# AFE_Only.net
KiCad netlist of a schematic drawn in EAGLE
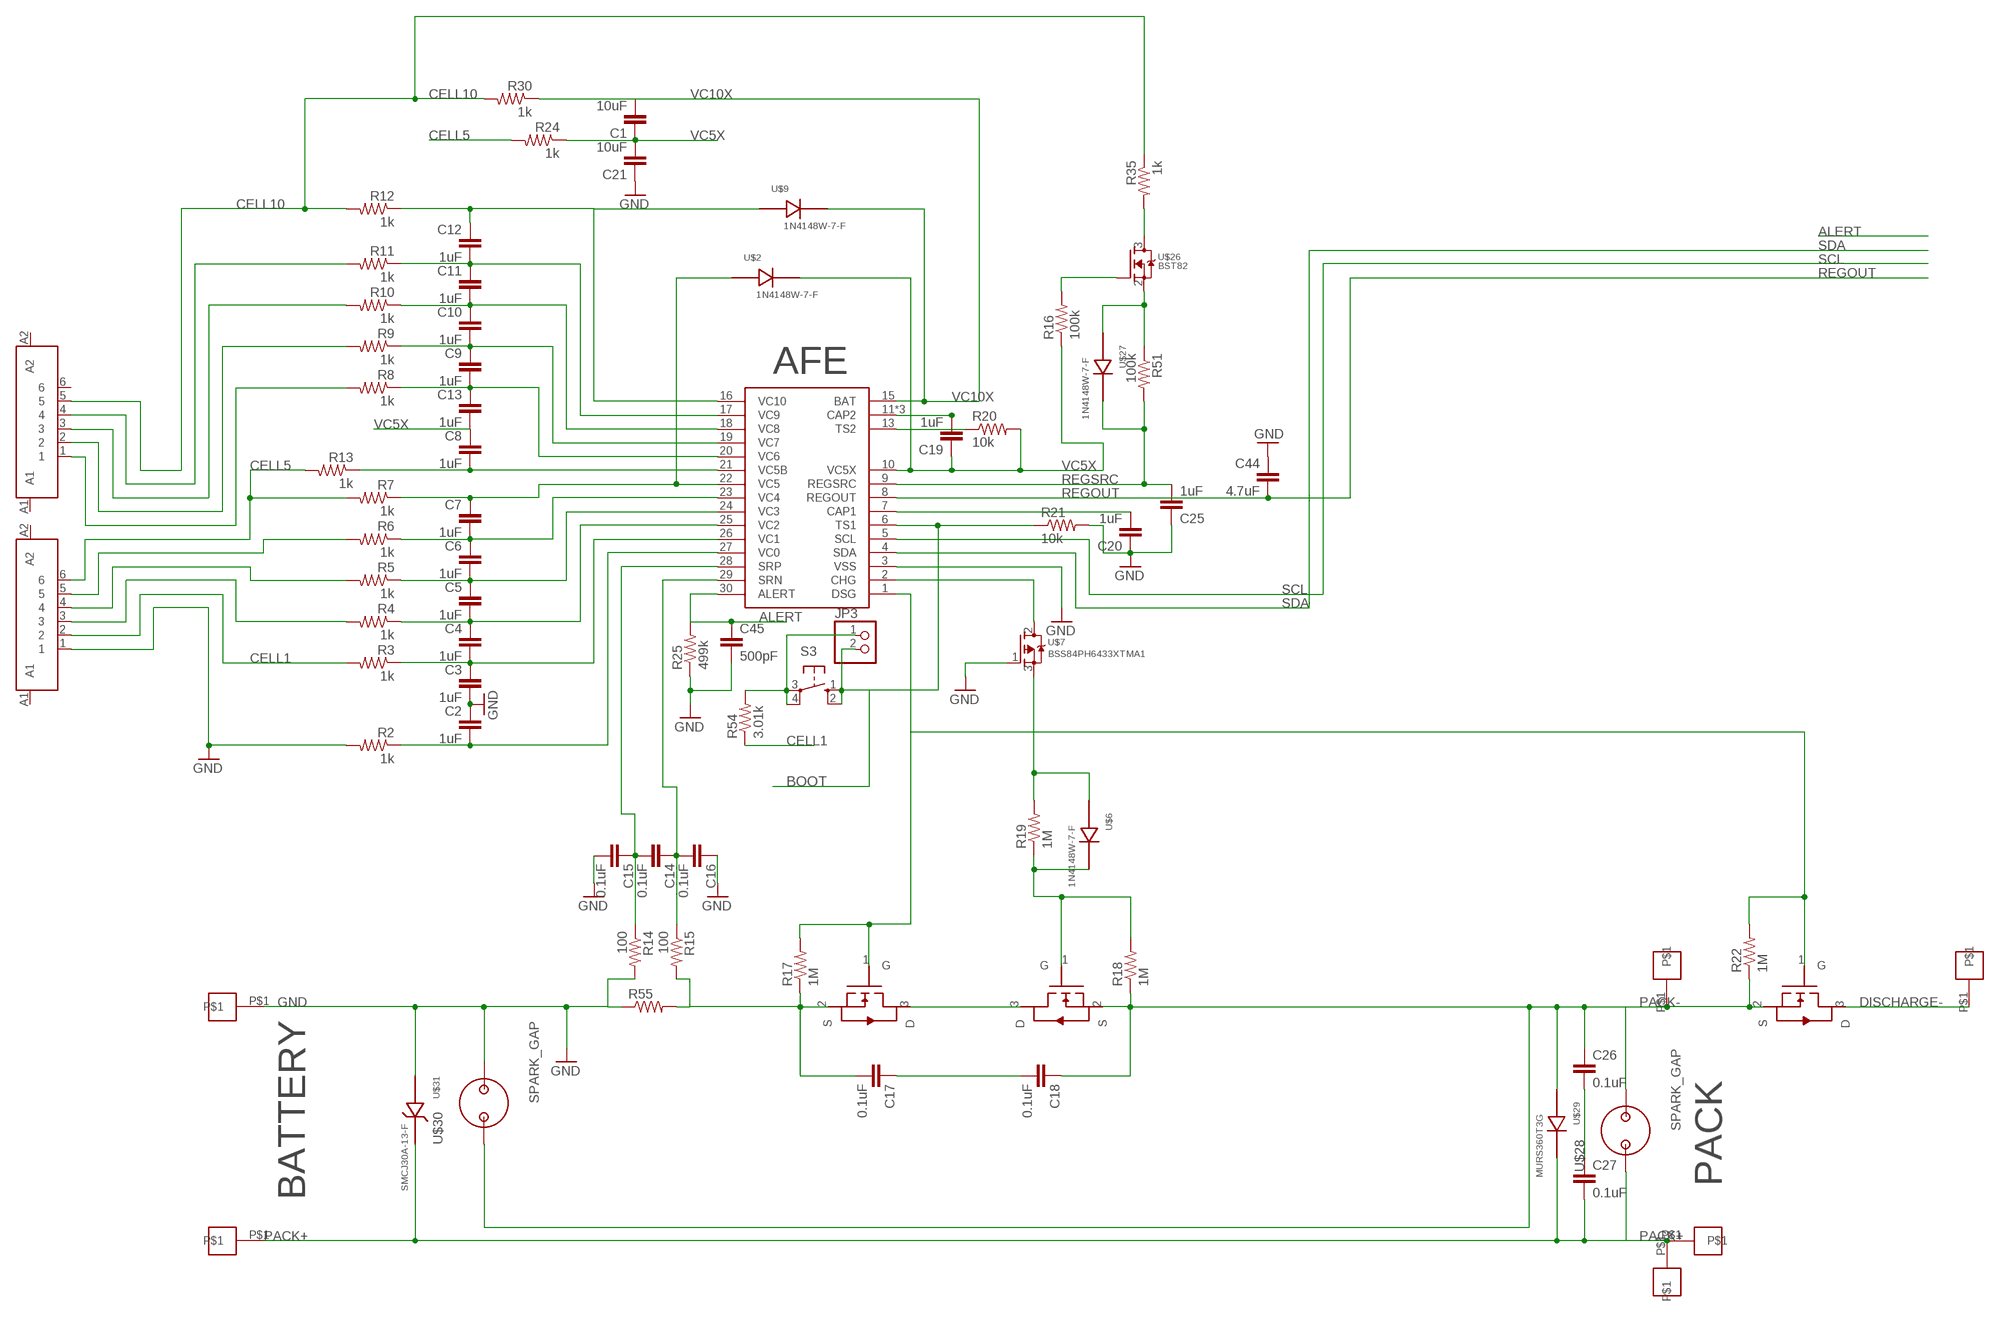
[diagram p0: schematic, sheet 1]
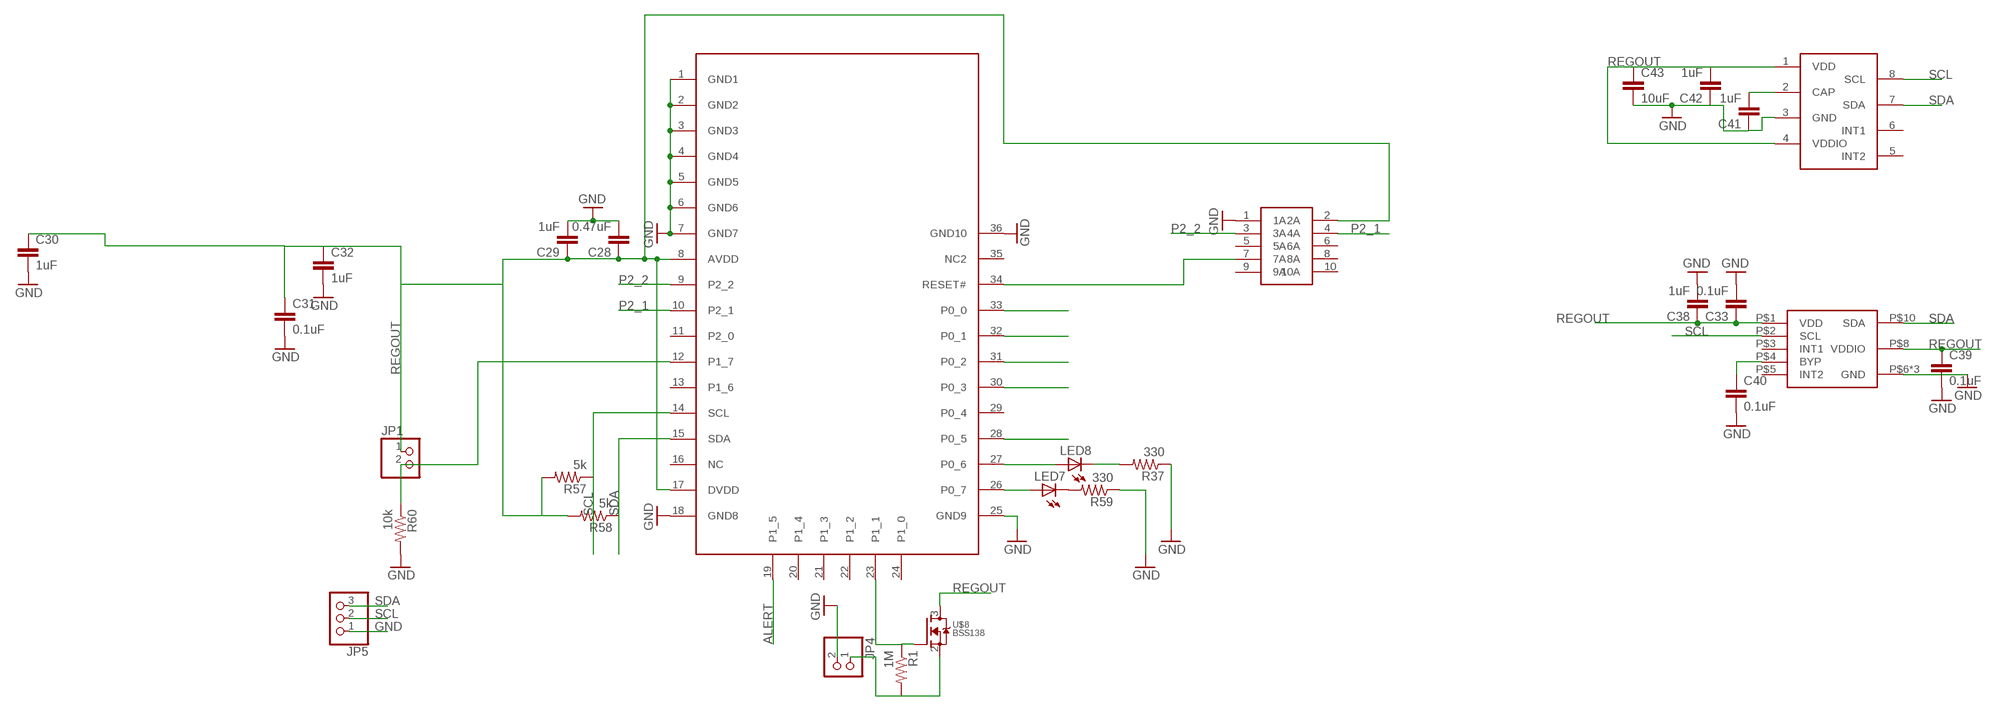
[diagram p1: schematic, sheet 2]

(export (version "E")
  (design (tool "Eeschema 10.0.6"))
  (components
    (comp (ref "C28")
      (value "0.47uF")
      (footprint "eagle-import:C0402")
      (libsource (lib "eagle-import") (part "C-EUC0402"))
    )
    (comp (ref "C29")
      (value "1uF")
      (footprint "eagle-import:C0402")
      (libsource (lib "eagle-import") (part "C-EUC0402"))
    )
    (comp (ref "C30")
      (value "1uF")
      (footprint "eagle-import:C0402")
      (libsource (lib "eagle-import") (part "C-EUC0402"))
    )
    (comp (ref "C31")
      (value "0.1uF")
      (footprint "eagle-import:C0402")
      (libsource (lib "eagle-import") (part "C-EUC0402"))
    )
    (comp (ref "C32")
      (value "1uF")
      (footprint "eagle-import:C0402")
      (libsource (lib "eagle-import") (part "C-EUC0402"))
    )
    (comp (ref "C33")
      (value "0.1uF")
      (footprint "eagle-import:C0402")
      (libsource (lib "eagle-import") (part "C-EUC0402"))
    )
    (comp (ref "C38")
      (value "1uF")
      (footprint "eagle-import:C0402")
      (libsource (lib "eagle-import") (part "C-EUC0402"))
    )
    (comp (ref "C39")
      (value "0.1uF")
      (footprint "eagle-import:C0402")
      (libsource (lib "eagle-import") (part "C-EUC0402"))
    )
    (comp (ref "C40")
      (value "0.1uF")
      (footprint "eagle-import:C0402")
      (libsource (lib "eagle-import") (part "C-EUC0402"))
    )
    (comp (ref "C41")
      (value "1uF")
      (footprint "eagle-import:C0402")
      (libsource (lib "eagle-import") (part "C-EUC0402"))
    )
    (comp (ref "C42")
      (value "1uF")
      (footprint "eagle-import:C0402")
      (libsource (lib "eagle-import") (part "C-EUC0402"))
    )
    (comp (ref "C43")
      (value "10uF")
      (footprint "eagle-import:C0603")
      (libsource (lib "eagle-import") (part "C-EUC0603"))
    )
    (comp (ref "JP1")
      (value "PINHD-1X2")
      (footprint "eagle-import:1X02")
      (libsource (lib "eagle-import") (part "PINHD-1X2"))
    )
    (comp (ref "JP4")
      (value "PINHD-1X2")
      (footprint "eagle-import:1X02")
      (libsource (lib "eagle-import") (part "PINHD-1X2"))
    )
    (comp (ref "JP5")
      (value "PINHD-1X3")
      (footprint "eagle-import:1X03")
      (libsource (lib "eagle-import") (part "PINHD-1X3"))
    )
    (comp (ref "LED7")
      (value "LEDCHIP-LED0603")
      (footprint "eagle-import:CHIP-LED0603")
      (libsource (lib "eagle-import") (part "LEDCHIP-LED0603"))
    )
    (comp (ref "LED8")
      (value "LEDCHIP-LED0603")
      (footprint "eagle-import:CHIP-LED0603")
      (libsource (lib "eagle-import") (part "LEDCHIP-LED0603"))
    )
    (comp (ref "R1")
      (value "1M")
      (footprint "eagle-import:R0402")
      (libsource (lib "eagle-import") (part "R-US_R0402"))
    )
    (comp (ref "R37")
      (value "330")
      (footprint "eagle-import:R0402")
      (libsource (lib "eagle-import") (part "R-US_R0402"))
    )
    (comp (ref "R57")
      (value "5k")
      (footprint "eagle-import:R0402")
      (libsource (lib "eagle-import") (part "R-US_R0402"))
    )
    (comp (ref "R58")
      (value "5k")
      (footprint "eagle-import:R0402")
      (libsource (lib "eagle-import") (part "R-US_R0402"))
    )
    (comp (ref "R59")
      (value "330")
      (footprint "eagle-import:R0402")
      (libsource (lib "eagle-import") (part "R-US_R0402"))
    )
    (comp (ref "R60")
      (value "10k")
      (footprint "eagle-import:R0402")
      (libsource (lib "eagle-import") (part "R-US_R0402"))
    )
    (comp (ref "U$8")
      (value "BSS138")
      (footprint "eagle-import:SOT23-3")
      (libsource (lib "eagle-import") (part "BSS138"))
    )
    (comp (ref "U$20")
      (value "BLE113")
      (footprint "eagle-import:BLUEGIGA")
      (libsource (lib "eagle-import") (part "BLE113"))
    )
    (comp (ref "U$22")
      (value "RIBBON_10POS_MALE")
      (footprint "eagle-import:RIBBON_10POS_MALE")
      (libsource (lib "eagle-import") (part "RIBBON_10POS_MALE"))
    )
    (comp (ref "U$25")
      (value "MLP3115A2")
      (footprint "eagle-import:MLP3115A2")
      (libsource (lib "eagle-import") (part "MLP3115A2"))
    )
    (comp (ref "U$32")
      (value "MMA8653FC")
      (footprint "eagle-import:10-DFN2X2")
      (libsource (lib "eagle-import") (part "MMA8653FC"))
    )
    (comp (ref "C1")
      (value "10uF")
      (footprint "eagle-import:C1210")
      (libsource (lib "eagle-import") (part "C-EUC1210"))
    )
    (comp (ref "C2")
      (value "1uF")
      (footprint "eagle-import:C0805")
      (libsource (lib "eagle-import") (part "C-EUC0805"))
    )
    (comp (ref "C3")
      (value "1uF")
      (footprint "eagle-import:C0805")
      (libsource (lib "eagle-import") (part "C-EUC0805"))
    )
    (comp (ref "C4")
      (value "1uF")
      (footprint "eagle-import:C0805")
      (libsource (lib "eagle-import") (part "C-EUC0805"))
    )
    (comp (ref "C5")
      (value "1uF")
      (footprint "eagle-import:C0805")
      (libsource (lib "eagle-import") (part "C-EUC0805"))
    )
    (comp (ref "C6")
      (value "1uF")
      (footprint "eagle-import:C0805")
      (libsource (lib "eagle-import") (part "C-EUC0805"))
    )
    (comp (ref "C7")
      (value "1uF")
      (footprint "eagle-import:C0805")
      (libsource (lib "eagle-import") (part "C-EUC0805"))
    )
    (comp (ref "C8")
      (value "1uF")
      (footprint "eagle-import:C0805")
      (libsource (lib "eagle-import") (part "C-EUC0805"))
    )
    (comp (ref "C9")
      (value "1uF")
      (footprint "eagle-import:C0805")
      (libsource (lib "eagle-import") (part "C-EUC0805"))
    )
    (comp (ref "C10")
      (value "1uF")
      (footprint "eagle-import:C0805")
      (libsource (lib "eagle-import") (part "C-EUC0805"))
    )
    (comp (ref "C11")
      (value "1uF")
      (footprint "eagle-import:C0805")
      (libsource (lib "eagle-import") (part "C-EUC0805"))
    )
    (comp (ref "C12")
      (value "1uF")
      (footprint "eagle-import:C0805")
      (libsource (lib "eagle-import") (part "C-EUC0805"))
    )
    (comp (ref "C13")
      (value "1uF")
      (footprint "eagle-import:C0805")
      (libsource (lib "eagle-import") (part "C-EUC0805"))
    )
    (comp (ref "C14")
      (value "0.1uF")
      (footprint "eagle-import:C0805")
      (libsource (lib "eagle-import") (part "C-EUC0805"))
    )
    (comp (ref "C15")
      (value "0.1uF")
      (footprint "eagle-import:C0805")
      (libsource (lib "eagle-import") (part "C-EUC0805"))
    )
    (comp (ref "C16")
      (value "0.1uF")
      (footprint "eagle-import:C0805")
      (libsource (lib "eagle-import") (part "C-EUC0805"))
    )
    (comp (ref "C17")
      (value "0.1uF")
      (footprint "eagle-import:C0805")
      (libsource (lib "eagle-import") (part "C-EUC0805"))
    )
    (comp (ref "C18")
      (value "0.1uF")
      (footprint "eagle-import:C0805")
      (libsource (lib "eagle-import") (part "C-EUC0805"))
    )
    (comp (ref "C19")
      (value "1uF")
      (footprint "eagle-import:C0805")
      (libsource (lib "eagle-import") (part "C-EUC0805"))
    )
    (comp (ref "C20")
      (value "1uF")
      (footprint "eagle-import:C0805")
      (libsource (lib "eagle-import") (part "C-EUC0805"))
    )
    (comp (ref "C21")
      (value "10uF")
      (footprint "eagle-import:C1210")
      (libsource (lib "eagle-import") (part "C-EUC1210"))
    )
    (comp (ref "C25")
      (value "1uF")
      (footprint "eagle-import:C0805")
      (libsource (lib "eagle-import") (part "C-EUC0805"))
    )
    (comp (ref "C26")
      (value "0.1uF")
      (footprint "eagle-import:C0805")
      (libsource (lib "eagle-import") (part "C-EUC0805"))
    )
    (comp (ref "C27")
      (value "0.1uF")
      (footprint "eagle-import:C0805")
      (libsource (lib "eagle-import") (part "C-EUC0805"))
    )
    (comp (ref "C44")
      (value "4.7uF")
      (footprint "eagle-import:C0805")
      (libsource (lib "eagle-import") (part "C-EUC0805"))
    )
    (comp (ref "C45")
      (value "500pF")
      (footprint "eagle-import:C0603")
      (libsource (lib "eagle-import") (part "C-EUC0603"))
    )
    (comp (ref "JP3")
      (value "PINHD-1X2")
      (footprint "eagle-import:1X02")
      (libsource (lib "eagle-import") (part "PINHD-1X2"))
    )
    (comp (ref "R2")
      (value "1k")
      (footprint "eagle-import:R1206")
      (libsource (lib "eagle-import") (part "R-US_R1206"))
    )
    (comp (ref "R3")
      (value "1k")
      (footprint "eagle-import:R1206")
      (libsource (lib "eagle-import") (part "R-US_R1206"))
    )
    (comp (ref "R4")
      (value "1k")
      (footprint "eagle-import:R1206")
      (libsource (lib "eagle-import") (part "R-US_R1206"))
    )
    (comp (ref "R5")
      (value "1k")
      (footprint "eagle-import:R1206")
      (libsource (lib "eagle-import") (part "R-US_R1206"))
    )
    (comp (ref "R6")
      (value "1k")
      (footprint "eagle-import:R1206")
      (libsource (lib "eagle-import") (part "R-US_R1206"))
    )
    (comp (ref "R7")
      (value "1k")
      (footprint "eagle-import:R1206")
      (libsource (lib "eagle-import") (part "R-US_R1206"))
    )
    (comp (ref "R8")
      (value "1k")
      (footprint "eagle-import:R1206")
      (libsource (lib "eagle-import") (part "R-US_R1206"))
    )
    (comp (ref "R9")
      (value "1k")
      (footprint "eagle-import:R1206")
      (libsource (lib "eagle-import") (part "R-US_R1206"))
    )
    (comp (ref "R10")
      (value "1k")
      (footprint "eagle-import:R1206")
      (libsource (lib "eagle-import") (part "R-US_R1206"))
    )
    (comp (ref "R11")
      (value "1k")
      (footprint "eagle-import:R1206")
      (libsource (lib "eagle-import") (part "R-US_R1206"))
    )
    (comp (ref "R12")
      (value "1k")
      (footprint "eagle-import:R1206")
      (libsource (lib "eagle-import") (part "R-US_R1206"))
    )
    (comp (ref "R13")
      (value "1k")
      (footprint "eagle-import:R1206")
      (libsource (lib "eagle-import") (part "R-US_R1206"))
    )
    (comp (ref "R14")
      (value "100")
      (footprint "eagle-import:R0805")
      (libsource (lib "eagle-import") (part "R-US_R0805"))
    )
    (comp (ref "R15")
      (value "100")
      (footprint "eagle-import:R0805")
      (libsource (lib "eagle-import") (part "R-US_R0805"))
    )
    (comp (ref "R16")
      (value "100k")
      (footprint "eagle-import:R0805")
      (libsource (lib "eagle-import") (part "R-US_R0805"))
    )
    (comp (ref "R17")
      (value "1M")
      (footprint "eagle-import:R1206")
      (libsource (lib "eagle-import") (part "R-US_R1206"))
    )
    (comp (ref "R18")
      (value "1M")
      (footprint "eagle-import:R1206")
      (libsource (lib "eagle-import") (part "R-US_R1206"))
    )
    (comp (ref "R19")
      (value "1M")
      (footprint "eagle-import:R1206")
      (libsource (lib "eagle-import") (part "R-US_R1206"))
    )
    (comp (ref "R20")
      (value "10k")
      (footprint "eagle-import:R0805")
      (libsource (lib "eagle-import") (part "R-US_R0805"))
    )
    (comp (ref "R21")
      (value "10k")
      (footprint "eagle-import:R0805")
      (libsource (lib "eagle-import") (part "R-US_R0805"))
    )
    (comp (ref "R22")
      (value "1M")
      (footprint "eagle-import:R1206")
      (libsource (lib "eagle-import") (part "R-US_R1206"))
    )
    (comp (ref "R24")
      (value "1k")
      (footprint "eagle-import:R1206")
      (libsource (lib "eagle-import") (part "R-US_R1206"))
    )
    (comp (ref "R25")
      (value "499k")
      (footprint "eagle-import:R0603")
      (libsource (lib "eagle-import") (part "R-US_R0603"))
    )
    (comp (ref "R30")
      (value "1k")
      (footprint "eagle-import:R1206")
      (libsource (lib "eagle-import") (part "R-US_R1206"))
    )
    (comp (ref "R35")
      (value "1k")
      (footprint "eagle-import:R1206")
      (libsource (lib "eagle-import") (part "R-US_R1206"))
    )
    (comp (ref "R51")
      (value "100k")
      (footprint "eagle-import:R0805")
      (libsource (lib "eagle-import") (part "R-US_R0805"))
    )
    (comp (ref "R54")
      (value "3.01k")
      (footprint "eagle-import:R1206")
      (libsource (lib "eagle-import") (part "R-US_R1206"))
    )
    (comp (ref "R55")
      (value "R-US_R2512")
      (footprint "eagle-import:R2512")
      (libsource (lib "eagle-import") (part "R-US_R2512"))
    )
    (comp (ref "S3")
      (value "10-XX")
      (footprint "eagle-import:B3F-10XX")
      (fields (field (name "MPN") "B3F-1000"))
      (libsource (lib "eagle-import") (part "10-XX"))
    )
    (comp (ref "U$1")
      (value "BQ76930")
      (footprint "eagle-import:SOIC-30")
      (libsource (lib "eagle-import") (part "BQ76930"))
    )
    (comp (ref "U$2")
      (value "1N4148W-7-F")
      (footprint "eagle-import:SOD-123")
      (libsource (lib "eagle-import") (part "1N4148W-7-F"))
    )
    (comp (ref "U$3")
      (value "PAD")
      (footprint "eagle-import:PAD")
      (libsource (lib "eagle-import") (part "PAD"))
    )
    (comp (ref "U$4")
      (value "AOB290L")
      (footprint "eagle-import:TO-263")
      (libsource (lib "eagle-import") (part "AOB290L"))
    )
    (comp (ref "U$5")
      (value "AOB290L")
      (footprint "eagle-import:TO-263")
      (libsource (lib "eagle-import") (part "AOB290L"))
    )
    (comp (ref "U$6")
      (value "1N4148W-7-F")
      (footprint "eagle-import:SOD-123")
      (libsource (lib "eagle-import") (part "1N4148W-7-F"))
    )
    (comp (ref "U$7")
      (value "BSS84PH6433XTMA1")
      (footprint "eagle-import:SOT23-3")
      (libsource (lib "eagle-import") (part "BSS84PH6433XTMA1"))
    )
    (comp (ref "U$9")
      (value "1N4148W-7-F")
      (footprint "eagle-import:SOD-123")
      (libsource (lib "eagle-import") (part "1N4148W-7-F"))
    )
    (comp (ref "U$10")
      (value "AOB290L")
      (footprint "eagle-import:TO-263")
      (libsource (lib "eagle-import") (part "AOB290L"))
    )
    (comp (ref "U$24")
      (value "JST_6PIN")
      (footprint "eagle-import:JST_6PIN")
      (libsource (lib "eagle-import") (part "JST_6PIN"))
    )
    (comp (ref "U$26")
      (value "BST82")
      (footprint "eagle-import:SOT23-3")
      (libsource (lib "eagle-import") (part "BST82"))
    )
    (comp (ref "U$27")
      (value "1N4148W-7-F")
      (footprint "eagle-import:SOD-123")
      (libsource (lib "eagle-import") (part "1N4148W-7-F"))
    )
    (comp (ref "U$28")
      (value "SPARK_GAP")
      (footprint "eagle-import:SPARK_GAP")
      (libsource (lib "eagle-import") (part "SPARK_GAP"))
    )
    (comp (ref "U$29")
      (value "MURS360T3G")
      (footprint "eagle-import:SMC(DO-214AB)")
      (libsource (lib "eagle-import") (part "MURS360T3G"))
    )
    (comp (ref "U$30")
      (value "SPARK_GAP")
      (footprint "eagle-import:SPARK_GAP")
      (libsource (lib "eagle-import") (part "SPARK_GAP"))
    )
    (comp (ref "U$31")
      (value "SMCJ30A-13-F")
      (footprint "eagle-import:SMB(DO-214AA)")
      (libsource (lib "eagle-import") (part "SMCJ30A-13-F"))
    )
    (comp (ref "U$33")
      (value "JST_6PIN")
      (footprint "eagle-import:JST_6PIN")
      (libsource (lib "eagle-import") (part "JST_6PIN"))
    )
    (comp (ref "U$35")
      (value "PAD")
      (footprint "eagle-import:PAD")
      (libsource (lib "eagle-import") (part "PAD"))
    )
    (comp (ref "U$36")
      (value "PAD")
      (footprint "eagle-import:PAD")
      (libsource (lib "eagle-import") (part "PAD"))
    )
    (comp (ref "U$37")
      (value "PAD")
      (footprint "eagle-import:PAD")
      (libsource (lib "eagle-import") (part "PAD"))
    )
    (comp (ref "U$38")
      (value "PAD")
      (footprint "eagle-import:PAD")
      (libsource (lib "eagle-import") (part "PAD"))
    )
    (comp (ref "U$39")
      (value "PAD")
      (footprint "eagle-import:PAD")
      (libsource (lib "eagle-import") (part "PAD"))
    )
  )
  (nets
    (net (code "1") (name "ALERT") (class "Default")
      (node (ref "C45") (pin "1") (pinfunction "1_1") (pintype "passive"))
      (node (ref "R25") (pin "2") (pinfunction "2_2") (pintype "passive"))
      (node (ref "U$1") (pin "30") (pinfunction "ALERT_30") (pintype "bidirectional"))
      (node (ref "U$20") (pin "19") (pinfunction "P1_5_19") (pintype "bidirectional"))
    )
    (net (code "2") (name "BOOT") (class "Default")
      (node (ref "JP3") (pin "2") (pinfunction "2_2") (pintype "passive"))
      (node (ref "R21") (pin "1") (pinfunction "1_1") (pintype "passive"))
      (node (ref "S3") (pin "1") (pinfunction "S_1") (pintype "passive"))
      (node (ref "S3") (pin "2") (pinfunction "S1_2") (pintype "passive"))
      (node (ref "U$1") (pin "6") (pinfunction "TS1_6") (pintype "bidirectional"))
    )
    (net (code "3") (name "CELL1") (class "Default")
      (node (ref "R3") (pin "2") (pinfunction "2_2") (pintype "passive"))
      (node (ref "R54") (pin "1") (pinfunction "1_1") (pintype "passive"))
      (node (ref "U$33") (pin "2") (pinfunction "2_2") (pintype "bidirectional"))
    )
    (net (code "4") (name "CELL5") (class "Default")
      (node (ref "R13") (pin "2") (pinfunction "2_2") (pintype "passive"))
      (node (ref "R24") (pin "2") (pinfunction "2_2") (pintype "passive"))
      (node (ref "R7") (pin "2") (pinfunction "2_2") (pintype "passive"))
      (node (ref "U$33") (pin "6") (pinfunction "6_6") (pintype "bidirectional"))
    )
    (net (code "5") (name "CELL10") (class "Default")
      (node (ref "R12") (pin "2") (pinfunction "2_2") (pintype "passive"))
      (node (ref "R30") (pin "2") (pinfunction "2_2") (pintype "passive"))
      (node (ref "R35") (pin "1") (pinfunction "1_1") (pintype "passive"))
      (node (ref "U$24") (pin "5") (pinfunction "5_5") (pintype "bidirectional"))
    )
    (net (code "6") (name "DISCHARGE-") (class "Default")
      (node (ref "U$10") (pin "3") (pinfunction "D_3") (pintype "bidirectional"))
      (node (ref "U$37") (pin "P$1") (pinfunction "P$1_P$1") (pintype "bidirectional"))
    )
    (net (code "7") (name "GND") (class "Default")
      (node (ref "C15") (pin "2") (pinfunction "2_2") (pintype "passive"))
      (node (ref "C16") (pin "1") (pinfunction "1_1") (pintype "passive"))
      (node (ref "C2") (pin "1") (pinfunction "1_1") (pintype "passive"))
      (node (ref "C20") (pin "1") (pinfunction "1_1") (pintype "passive"))
      (node (ref "C21") (pin "1") (pinfunction "1_1") (pintype "passive"))
      (node (ref "C25") (pin "1") (pinfunction "1_1") (pintype "passive"))
      (node (ref "C28") (pin "2") (pinfunction "2_2") (pintype "passive"))
      (node (ref "C29") (pin "2") (pinfunction "2_2") (pintype "passive"))
      (node (ref "C3") (pin "2") (pinfunction "2_2") (pintype "passive"))
      (node (ref "C30") (pin "2") (pinfunction "2_2") (pintype "passive"))
      (node (ref "C31") (pin "2") (pinfunction "2_2") (pintype "passive"))
      (node (ref "C32") (pin "2") (pinfunction "2_2") (pintype "passive"))
      (node (ref "C33") (pin "2") (pinfunction "2_2") (pintype "passive"))
      (node (ref "C38") (pin "2") (pinfunction "2_2") (pintype "passive"))
      (node (ref "C39") (pin "2") (pinfunction "2_2") (pintype "passive"))
      (node (ref "C40") (pin "2") (pinfunction "2_2") (pintype "passive"))
      (node (ref "C41") (pin "1") (pinfunction "1_1") (pintype "passive"))
      (node (ref "C42") (pin "1") (pinfunction "1_1") (pintype "passive"))
      (node (ref "C43") (pin "2") (pinfunction "2_2") (pintype "passive"))
      (node (ref "C44") (pin "1") (pinfunction "1_1") (pintype "passive"))
      (node (ref "C45") (pin "2") (pinfunction "2_2") (pintype "passive"))
      (node (ref "JP4") (pin "2") (pinfunction "2_2") (pintype "passive"))
      (node (ref "JP5") (pin "1") (pinfunction "1_1") (pintype "passive"))
      (node (ref "R14") (pin "2") (pinfunction "2_2") (pintype "passive"))
      (node (ref "R2") (pin "2") (pinfunction "2_2") (pintype "passive"))
      (node (ref "R21") (pin "2") (pinfunction "2_2") (pintype "passive"))
      (node (ref "R25") (pin "1") (pinfunction "1_1") (pintype "passive"))
      (node (ref "R37") (pin "1") (pinfunction "1_1") (pintype "passive"))
      (node (ref "R55") (pin "1") (pinfunction "1_1") (pintype "passive"))
      (node (ref "R59") (pin "1") (pinfunction "1_1") (pintype "passive"))
      (node (ref "R60") (pin "2") (pinfunction "2_2") (pintype "passive"))
      (node (ref "U$1") (pin "3") (pinfunction "VSS_3") (pintype "bidirectional"))
      (node (ref "U$20") (pin "1") (pinfunction "GND1_1") (pintype "bidirectional"))
      (node (ref "U$20") (pin "18") (pinfunction "GND8_18") (pintype "bidirectional"))
      (node (ref "U$20") (pin "2") (pinfunction "GND2_2") (pintype "bidirectional"))
      (node (ref "U$20") (pin "25") (pinfunction "GND9_25") (pintype "bidirectional"))
      (node (ref "U$20") (pin "3") (pinfunction "GND3_3") (pintype "bidirectional"))
      (node (ref "U$20") (pin "36") (pinfunction "GND10_36") (pintype "bidirectional"))
      (node (ref "U$20") (pin "4") (pinfunction "GND4_4") (pintype "bidirectional"))
      (node (ref "U$20") (pin "5") (pinfunction "GND5_5") (pintype "bidirectional"))
      (node (ref "U$20") (pin "6") (pinfunction "GND6_6") (pintype "bidirectional"))
      (node (ref "U$20") (pin "7") (pinfunction "GND7_7") (pintype "bidirectional"))
      (node (ref "U$22") (pin "1") (pinfunction "1A_1") (pintype "bidirectional"))
      (node (ref "U$25") (pin "3") (pinfunction "GND_3") (pintype "bidirectional"))
      (node (ref "U$3") (pin "P$1") (pinfunction "P$1_P$1") (pintype "bidirectional"))
      (node (ref "U$30") (pin "P$2") (pinfunction "P$2_P$2") (pintype "bidirectional"))
      (node (ref "U$31") (pin "P$1") (pinfunction "1_P$1") (pintype "bidirectional"))
      (node (ref "U$32") (pin "P$6") (pinfunction "GND_P$6") (pintype "bidirectional"))
      (node (ref "U$32") (pin "P$7") (pinfunction "GND_P$7") (pintype "bidirectional"))
      (node (ref "U$32") (pin "P$9") (pinfunction "GND_P$9") (pintype "bidirectional"))
      (node (ref "U$33") (pin "1") (pinfunction "1_1") (pintype "bidirectional"))
      (node (ref "U$7") (pin "1") (pinfunction "G_1") (pintype "bidirectional"))
    )
    (net (code "8") (name "Net-(C17-Pad1)") (class "Default")
      (node (ref "C17") (pin "1") (pinfunction "1_1") (pintype "passive"))
      (node (ref "C18") (pin "2") (pinfunction "2_2") (pintype "passive"))
    )
    (net (code "9") (name "Net-(C19-Pad2)") (class "Default")
      (node (ref "C19") (pin "2") (pinfunction "2_2") (pintype "passive"))
      (node (ref "U$1") (pin "11") (pinfunction "CAP2_11") (pintype "bidirectional"))
      (node (ref "U$1") (pin "12") (pinfunction "CAP2_12") (pintype "bidirectional"))
      (node (ref "U$1") (pin "14") (pinfunction "CAP2_14") (pintype "bidirectional"))
    )
    (net (code "10") (name "Net-(C26-Pad2)") (class "Default")
      (node (ref "C26") (pin "2") (pinfunction "2_2") (pintype "passive"))
      (node (ref "C27") (pin "1") (pinfunction "1_1") (pintype "passive"))
    )
    (net (code "11") (name "Net-(LED7-PadC)") (class "Default")
      (node (ref "LED7") (pin "C") (pinfunction "C_C") (pintype "passive"))
      (node (ref "R59") (pin "2") (pinfunction "2_2") (pintype "passive"))
    )
    (net (code "12") (name "Net-(LED8-PadC)") (class "Default")
      (node (ref "LED8") (pin "C") (pinfunction "C_C") (pintype "passive"))
      (node (ref "R37") (pin "2") (pinfunction "2_2") (pintype "passive"))
    )
    (net (code "13") (name "Net-(R4-Pad2)") (class "Default")
      (node (ref "R4") (pin "2") (pinfunction "2_2") (pintype "passive"))
      (node (ref "U$33") (pin "3") (pinfunction "3_3") (pintype "bidirectional"))
    )
    (net (code "14") (name "Net-(R5-Pad2)") (class "Default")
      (node (ref "R5") (pin "2") (pinfunction "2_2") (pintype "passive"))
      (node (ref "U$33") (pin "4") (pinfunction "4_4") (pintype "bidirectional"))
    )
    (net (code "15") (name "Net-(R6-Pad2)") (class "Default")
      (node (ref "R6") (pin "2") (pinfunction "2_2") (pintype "passive"))
      (node (ref "U$33") (pin "5") (pinfunction "5_5") (pintype "bidirectional"))
    )
    (net (code "16") (name "Net-(R8-Pad2)") (class "Default")
      (node (ref "R8") (pin "2") (pinfunction "2_2") (pintype "passive"))
      (node (ref "U$24") (pin "1") (pinfunction "1_1") (pintype "bidirectional"))
    )
    (net (code "17") (name "Net-(R9-Pad2)") (class "Default")
      (node (ref "R9") (pin "2") (pinfunction "2_2") (pintype "passive"))
      (node (ref "U$24") (pin "2") (pinfunction "2_2") (pintype "bidirectional"))
    )
    (net (code "18") (name "Net-(R10-Pad2)") (class "Default")
      (node (ref "R10") (pin "2") (pinfunction "2_2") (pintype "passive"))
      (node (ref "U$24") (pin "3") (pinfunction "3_3") (pintype "bidirectional"))
    )
    (net (code "19") (name "Net-(R11-Pad2)") (class "Default")
      (node (ref "R11") (pin "2") (pinfunction "2_2") (pintype "passive"))
      (node (ref "U$24") (pin "4") (pinfunction "4_4") (pintype "bidirectional"))
    )
    (net (code "20") (name "Net-(S3-P)") (class "Default")
      (node (ref "JP3") (pin "1") (pinfunction "1_1") (pintype "passive"))
      (node (ref "R54") (pin "2") (pinfunction "2_2") (pintype "passive"))
      (node (ref "S3") (pin "3") (pinfunction "P_3") (pintype "passive"))
      (node (ref "S3") (pin "4") (pinfunction "P1_4") (pintype "passive"))
    )
    (net (code "21") (name "Net-(U$1-CAP1)") (class "Default")
      (node (ref "C20") (pin "2") (pinfunction "2_2") (pintype "passive"))
      (node (ref "U$1") (pin "7") (pinfunction "CAP1_7") (pintype "bidirectional"))
    )
    (net (code "22") (name "Net-(U$1-CHG)") (class "Default")
      (node (ref "U$1") (pin "2") (pinfunction "CHG_2") (pintype "bidirectional"))
      (node (ref "U$7") (pin "2") (pinfunction "S_2") (pintype "bidirectional"))
    )
    (net (code "23") (name "Net-(U$1-DSG)") (class "Default")
      (node (ref "R17") (pin "2") (pinfunction "2_2") (pintype "passive"))
      (node (ref "R22") (pin "2") (pinfunction "2_2") (pintype "passive"))
      (node (ref "U$1") (pin "1") (pinfunction "DSG_1") (pintype "bidirectional"))
      (node (ref "U$10") (pin "1") (pinfunction "G_1") (pintype "bidirectional"))
      (node (ref "U$4") (pin "1") (pinfunction "G_1") (pintype "bidirectional"))
    )
    (net (code "24") (name "Net-(U$1-SRN)") (class "Default")
      (node (ref "C14") (pin "1") (pinfunction "1_1") (pintype "passive"))
      (node (ref "C16") (pin "2") (pinfunction "2_2") (pintype "passive"))
      (node (ref "R15") (pin "1") (pinfunction "1_1") (pintype "passive"))
      (node (ref "U$1") (pin "29") (pinfunction "SRN_29") (pintype "bidirectional"))
    )
    (net (code "25") (name "Net-(U$1-SRP)") (class "Default")
      (node (ref "C14") (pin "2") (pinfunction "2_2") (pintype "passive"))
      (node (ref "C15") (pin "1") (pinfunction "1_1") (pintype "passive"))
      (node (ref "R14") (pin "1") (pinfunction "1_1") (pintype "passive"))
      (node (ref "U$1") (pin "28") (pinfunction "SRP_28") (pintype "bidirectional"))
    )
    (net (code "26") (name "Net-(U$1-TS2)") (class "Default")
      (node (ref "R20") (pin "1") (pinfunction "1_1") (pintype "passive"))
      (node (ref "U$1") (pin "13") (pinfunction "TS2_13") (pintype "bidirectional"))
    )
    (net (code "27") (name "Net-(U$1-VC0)") (class "Default")
      (node (ref "C2") (pin "2") (pinfunction "2_2") (pintype "passive"))
      (node (ref "R2") (pin "1") (pinfunction "1_1") (pintype "passive"))
      (node (ref "U$1") (pin "27") (pinfunction "VC0_27") (pintype "bidirectional"))
    )
    (net (code "28") (name "Net-(U$1-VC1)") (class "Default")
      (node (ref "C3") (pin "1") (pinfunction "1_1") (pintype "passive"))
      (node (ref "C4") (pin "2") (pinfunction "2_2") (pintype "passive"))
      (node (ref "R3") (pin "1") (pinfunction "1_1") (pintype "passive"))
      (node (ref "U$1") (pin "26") (pinfunction "VC1_26") (pintype "bidirectional"))
    )
    (net (code "29") (name "Net-(U$1-VC2)") (class "Default")
      (node (ref "C4") (pin "1") (pinfunction "1_1") (pintype "passive"))
      (node (ref "C5") (pin "2") (pinfunction "2_2") (pintype "passive"))
      (node (ref "R4") (pin "1") (pinfunction "1_1") (pintype "passive"))
      (node (ref "U$1") (pin "25") (pinfunction "VC2_25") (pintype "bidirectional"))
    )
    (net (code "30") (name "Net-(U$1-VC3)") (class "Default")
      (node (ref "C5") (pin "1") (pinfunction "1_1") (pintype "passive"))
      (node (ref "C6") (pin "2") (pinfunction "2_2") (pintype "passive"))
      (node (ref "R5") (pin "1") (pinfunction "1_1") (pintype "passive"))
      (node (ref "U$1") (pin "24") (pinfunction "VC3_24") (pintype "bidirectional"))
    )
    (net (code "31") (name "Net-(U$1-VC4)") (class "Default")
      (node (ref "C6") (pin "1") (pinfunction "1_1") (pintype "passive"))
      (node (ref "C7") (pin "2") (pinfunction "2_2") (pintype "passive"))
      (node (ref "R6") (pin "1") (pinfunction "1_1") (pintype "passive"))
      (node (ref "U$1") (pin "23") (pinfunction "VC4_23") (pintype "bidirectional"))
    )
    (net (code "32") (name "Net-(U$1-VC5)") (class "Default")
      (node (ref "C7") (pin "1") (pinfunction "1_1") (pintype "passive"))
      (node (ref "R7") (pin "1") (pinfunction "1_1") (pintype "passive"))
      (node (ref "U$1") (pin "22") (pinfunction "VC5_22") (pintype "bidirectional"))
      (node (ref "U$2") (pin "P$1") (pinfunction "P$1_P$1") (pintype "bidirectional"))
    )
    (net (code "33") (name "Net-(U$1-VC5B)") (class "Default")
      (node (ref "C8") (pin "2") (pinfunction "2_2") (pintype "passive"))
      (node (ref "R13") (pin "1") (pinfunction "1_1") (pintype "passive"))
      (node (ref "U$1") (pin "21") (pinfunction "VC5B_21") (pintype "bidirectional"))
    )
    (net (code "34") (name "Net-(U$1-VC6)") (class "Default")
      (node (ref "C13") (pin "1") (pinfunction "1_1") (pintype "passive"))
      (node (ref "C9") (pin "2") (pinfunction "2_2") (pintype "passive"))
      (node (ref "R8") (pin "1") (pinfunction "1_1") (pintype "passive"))
      (node (ref "U$1") (pin "20") (pinfunction "VC6_20") (pintype "bidirectional"))
    )
    (net (code "35") (name "Net-(U$1-VC7)") (class "Default")
      (node (ref "C10") (pin "2") (pinfunction "2_2") (pintype "passive"))
      (node (ref "C9") (pin "1") (pinfunction "1_1") (pintype "passive"))
      (node (ref "R9") (pin "1") (pinfunction "1_1") (pintype "passive"))
      (node (ref "U$1") (pin "19") (pinfunction "VC7_19") (pintype "bidirectional"))
    )
    (net (code "36") (name "Net-(U$1-VC8)") (class "Default")
      (node (ref "C10") (pin "1") (pinfunction "1_1") (pintype "passive"))
      (node (ref "C11") (pin "2") (pinfunction "2_2") (pintype "passive"))
      (node (ref "R10") (pin "1") (pinfunction "1_1") (pintype "passive"))
      (node (ref "U$1") (pin "18") (pinfunction "VC8_18") (pintype "bidirectional"))
    )
    (net (code "37") (name "Net-(U$1-VC9)") (class "Default")
      (node (ref "C11") (pin "1") (pinfunction "1_1") (pintype "passive"))
      (node (ref "C12") (pin "2") (pinfunction "2_2") (pintype "passive"))
      (node (ref "R11") (pin "1") (pinfunction "1_1") (pintype "passive"))
      (node (ref "U$1") (pin "17") (pinfunction "VC9_17") (pintype "bidirectional"))
    )
    (net (code "38") (name "Net-(U$1-VC10)") (class "Default")
      (node (ref "C12") (pin "1") (pinfunction "1_1") (pintype "passive"))
      (node (ref "R12") (pin "1") (pinfunction "1_1") (pintype "passive"))
      (node (ref "U$1") (pin "16") (pinfunction "VC10_16") (pintype "bidirectional"))
      (node (ref "U$9") (pin "P$1") (pinfunction "P$1_P$1") (pintype "bidirectional"))
    )
    (net (code "39") (name "Net-(U$4-D)") (class "Default")
      (node (ref "U$4") (pin "3") (pinfunction "D_3") (pintype "bidirectional"))
      (node (ref "U$5") (pin "3") (pinfunction "D_3") (pintype "bidirectional"))
    )
    (net (code "40") (name "Net-(U$4-S)") (class "Default")
      (node (ref "C17") (pin "2") (pinfunction "2_2") (pintype "passive"))
      (node (ref "R15") (pin "2") (pinfunction "2_2") (pintype "passive"))
      (node (ref "R17") (pin "1") (pinfunction "1_1") (pintype "passive"))
      (node (ref "R55") (pin "2") (pinfunction "2_2") (pintype "passive"))
      (node (ref "U$4") (pin "2") (pinfunction "S_2") (pintype "bidirectional"))
    )
    (net (code "41") (name "Net-(U$5-G)") (class "Default")
      (node (ref "R18") (pin "2") (pinfunction "2_2") (pintype "passive"))
      (node (ref "R19") (pin "1") (pinfunction "1_1") (pintype "passive"))
      (node (ref "U$5") (pin "1") (pinfunction "G_1") (pintype "bidirectional"))
      (node (ref "U$6") (pin "P$2") (pinfunction "P$2_P$2") (pintype "bidirectional"))
    )
    (net (code "42") (name "Net-(U$7-D)") (class "Default")
      (node (ref "R19") (pin "2") (pinfunction "2_2") (pintype "passive"))
      (node (ref "U$6") (pin "P$1") (pinfunction "P$1_P$1") (pintype "bidirectional"))
      (node (ref "U$7") (pin "3") (pinfunction "D_3") (pintype "bidirectional"))
    )
    (net (code "43") (name "Net-(U$8-S)") (class "Default")
      (node (ref "JP4") (pin "1") (pinfunction "1_1") (pintype "passive"))
      (node (ref "R1") (pin "2") (pinfunction "2_2") (pintype "passive"))
      (node (ref "U$8") (pin "2") (pinfunction "S_2") (pintype "bidirectional"))
    )
    (net (code "44") (name "Net-(U$20-P0_6)") (class "Default")
      (node (ref "LED8") (pin "A") (pinfunction "A_A") (pintype "passive"))
      (node (ref "U$20") (pin "27") (pinfunction "P0_6_27") (pintype "bidirectional"))
    )
    (net (code "45") (name "Net-(U$20-P0_7)") (class "Default")
      (node (ref "LED7") (pin "A") (pinfunction "A_A") (pintype "passive"))
      (node (ref "U$20") (pin "26") (pinfunction "P0_7_26") (pintype "bidirectional"))
    )
    (net (code "46") (name "Net-(U$20-P1_1)") (class "Default")
      (node (ref "R1") (pin "1") (pinfunction "1_1") (pintype "passive"))
      (node (ref "U$20") (pin "23") (pinfunction "P1_1_23") (pintype "bidirectional"))
      (node (ref "U$8") (pin "1") (pinfunction "G_1") (pintype "bidirectional"))
    )
    (net (code "47") (name "Net-(U$20-P1_7)") (class "Default")
      (node (ref "JP1") (pin "2") (pinfunction "2_2") (pintype "passive"))
      (node (ref "R60") (pin "1") (pinfunction "1_1") (pintype "passive"))
      (node (ref "U$20") (pin "12") (pinfunction "P1_7_12") (pintype "bidirectional"))
    )
    (net (code "48") (name "Net-(U$20-RESET#)") (class "Default")
      (node (ref "U$20") (pin "34") (pinfunction "RESET#_34") (pintype "bidirectional"))
      (node (ref "U$22") (pin "7") (pinfunction "7A_7") (pintype "bidirectional"))
    )
    (net (code "49") (name "Net-(U$25-CAP)") (class "Default")
      (node (ref "C41") (pin "2") (pinfunction "2_2") (pintype "passive"))
      (node (ref "U$25") (pin "2") (pinfunction "CAP_2") (pintype "bidirectional"))
    )
    (net (code "50") (name "Net-(U$26-D)") (class "Default")
      (node (ref "R35") (pin "2") (pinfunction "2_2") (pintype "passive"))
      (node (ref "U$26") (pin "3") (pinfunction "D_3") (pintype "bidirectional"))
    )
    (net (code "51") (name "Net-(U$26-G)") (class "Default")
      (node (ref "R16") (pin "2") (pinfunction "2_2") (pintype "passive"))
      (node (ref "U$26") (pin "1") (pinfunction "G_1") (pintype "bidirectional"))
    )
    (net (code "52") (name "Net-(U$26-S)") (class "Default")
      (node (ref "R51") (pin "1") (pinfunction "1_1") (pintype "passive"))
      (node (ref "U$26") (pin "2") (pinfunction "S_2") (pintype "bidirectional"))
      (node (ref "U$27") (pin "P$1") (pinfunction "P$1_P$1") (pintype "bidirectional"))
    )
    (net (code "53") (name "Net-(U$32-BYP)") (class "Default")
      (node (ref "C40") (pin "1") (pinfunction "1_1") (pintype "passive"))
      (node (ref "U$32") (pin "P$4") (pinfunction "BYP_P$4") (pintype "bidirectional"))
    )
    (net (code "54") (name "P2_1") (class "Default")
      (node (ref "U$20") (pin "10") (pinfunction "P2_1_10") (pintype "bidirectional"))
      (node (ref "U$22") (pin "4") (pinfunction "4A_4") (pintype "bidirectional"))
    )
    (net (code "55") (name "P2_2") (class "Default")
      (node (ref "U$20") (pin "9") (pinfunction "P2_2_9") (pintype "bidirectional"))
      (node (ref "U$22") (pin "3") (pinfunction "3A_3") (pintype "bidirectional"))
    )
    (net (code "56") (name "PACK+") (class "Default")
      (node (ref "C27") (pin "2") (pinfunction "2_2") (pintype "passive"))
      (node (ref "U$28") (pin "P$1") (pinfunction "P$1_P$1") (pintype "bidirectional"))
      (node (ref "U$29") (pin "2") (pinfunction "P$2_2") (pintype "bidirectional"))
      (node (ref "U$31") (pin "P$2") (pinfunction "2_P$2") (pintype "bidirectional"))
      (node (ref "U$35") (pin "P$1") (pinfunction "P$1_P$1") (pintype "bidirectional"))
      (node (ref "U$36") (pin "P$1") (pinfunction "P$1_P$1") (pintype "bidirectional"))
      (node (ref "U$39") (pin "P$1") (pinfunction "P$1_P$1") (pintype "bidirectional"))
    )
    (net (code "57") (name "PACK-") (class "Default")
      (node (ref "C18") (pin "1") (pinfunction "1_1") (pintype "passive"))
      (node (ref "C26") (pin "1") (pinfunction "1_1") (pintype "passive"))
      (node (ref "R18") (pin "1") (pinfunction "1_1") (pintype "passive"))
      (node (ref "R22") (pin "1") (pinfunction "1_1") (pintype "passive"))
      (node (ref "U$10") (pin "2") (pinfunction "S_2") (pintype "bidirectional"))
      (node (ref "U$28") (pin "P$2") (pinfunction "P$2_P$2") (pintype "bidirectional"))
      (node (ref "U$29") (pin "1") (pinfunction "P$1_1") (pintype "bidirectional"))
      (node (ref "U$30") (pin "P$1") (pinfunction "P$1_P$1") (pintype "bidirectional"))
      (node (ref "U$38") (pin "P$1") (pinfunction "P$1_P$1") (pintype "bidirectional"))
      (node (ref "U$5") (pin "2") (pinfunction "S_2") (pintype "bidirectional"))
    )
    (net (code "58") (name "REGOUT") (class "Default")
      (node (ref "C28") (pin "1") (pinfunction "1_1") (pintype "passive"))
      (node (ref "C29") (pin "1") (pinfunction "1_1") (pintype "passive"))
      (node (ref "C30") (pin "1") (pinfunction "1_1") (pintype "passive"))
      (node (ref "C31") (pin "1") (pinfunction "1_1") (pintype "passive"))
      (node (ref "C32") (pin "1") (pinfunction "1_1") (pintype "passive"))
      (node (ref "C33") (pin "1") (pinfunction "1_1") (pintype "passive"))
      (node (ref "C38") (pin "1") (pinfunction "1_1") (pintype "passive"))
      (node (ref "C39") (pin "1") (pinfunction "1_1") (pintype "passive"))
      (node (ref "C42") (pin "2") (pinfunction "2_2") (pintype "passive"))
      (node (ref "C43") (pin "1") (pinfunction "1_1") (pintype "passive"))
      (node (ref "C44") (pin "2") (pinfunction "2_2") (pintype "passive"))
      (node (ref "JP1") (pin "1") (pinfunction "1_1") (pintype "passive"))
      (node (ref "R57") (pin "2") (pinfunction "2_2") (pintype "passive"))
      (node (ref "R58") (pin "2") (pinfunction "2_2") (pintype "passive"))
      (node (ref "U$1") (pin "8") (pinfunction "REGOUT_8") (pintype "bidirectional"))
      (node (ref "U$20") (pin "17") (pinfunction "DVDD_17") (pintype "bidirectional"))
      (node (ref "U$20") (pin "8") (pinfunction "AVDD_8") (pintype "bidirectional"))
      (node (ref "U$22") (pin "2") (pinfunction "2A_2") (pintype "bidirectional"))
      (node (ref "U$25") (pin "1") (pinfunction "VDD_1") (pintype "bidirectional"))
      (node (ref "U$25") (pin "4") (pinfunction "VDDIO_4") (pintype "bidirectional"))
      (node (ref "U$32") (pin "P$1") (pinfunction "VDD_P$1") (pintype "bidirectional"))
      (node (ref "U$32") (pin "P$8") (pinfunction "VDDIO_P$8") (pintype "bidirectional"))
      (node (ref "U$8") (pin "3") (pinfunction "D_3") (pintype "bidirectional"))
    )
    (net (code "59") (name "REGSRC") (class "Default")
      (node (ref "C25") (pin "2") (pinfunction "2_2") (pintype "passive"))
      (node (ref "R51") (pin "2") (pinfunction "2_2") (pintype "passive"))
      (node (ref "U$1") (pin "9") (pinfunction "REGSRC_9") (pintype "bidirectional"))
      (node (ref "U$27") (pin "P$2") (pinfunction "P$2_P$2") (pintype "bidirectional"))
    )
    (net (code "60") (name "SCL") (class "Default")
      (node (ref "JP5") (pin "2") (pinfunction "2_2") (pintype "passive"))
      (node (ref "R57") (pin "1") (pinfunction "1_1") (pintype "passive"))
      (node (ref "U$1") (pin "5") (pinfunction "SCL_5") (pintype "bidirectional"))
      (node (ref "U$20") (pin "14") (pinfunction "SCL_14") (pintype "bidirectional"))
      (node (ref "U$25") (pin "8") (pinfunction "SCL_8") (pintype "bidirectional"))
      (node (ref "U$32") (pin "P$2") (pinfunction "SCL_P$2") (pintype "bidirectional"))
    )
    (net (code "61") (name "SDA") (class "Default")
      (node (ref "JP5") (pin "3") (pinfunction "3_3") (pintype "passive"))
      (node (ref "R58") (pin "1") (pinfunction "1_1") (pintype "passive"))
      (node (ref "U$1") (pin "4") (pinfunction "SDA_4") (pintype "bidirectional"))
      (node (ref "U$20") (pin "15") (pinfunction "SDA_15") (pintype "bidirectional"))
      (node (ref "U$25") (pin "7") (pinfunction "SDA_7") (pintype "bidirectional"))
      (node (ref "U$32") (pin "P$10") (pinfunction "SDA_P$10") (pintype "bidirectional"))
    )
    (net (code "62") (name "VC5X") (class "Default")
      (node (ref "C1") (pin "1") (pinfunction "1_1") (pintype "passive"))
      (node (ref "C13") (pin "2") (pinfunction "2_2") (pintype "passive"))
      (node (ref "C19") (pin "1") (pinfunction "1_1") (pintype "passive"))
      (node (ref "C21") (pin "2") (pinfunction "2_2") (pintype "passive"))
      (node (ref "C8") (pin "1") (pinfunction "1_1") (pintype "passive"))
      (node (ref "R16") (pin "1") (pinfunction "1_1") (pintype "passive"))
      (node (ref "R20") (pin "2") (pinfunction "2_2") (pintype "passive"))
      (node (ref "R24") (pin "1") (pinfunction "1_1") (pintype "passive"))
      (node (ref "U$1") (pin "10") (pinfunction "VC5X_10") (pintype "bidirectional"))
      (node (ref "U$2") (pin "P$2") (pinfunction "P$2_P$2") (pintype "bidirectional"))
    )
    (net (code "63") (name "VC10X") (class "Default")
      (node (ref "C1") (pin "2") (pinfunction "2_2") (pintype "passive"))
      (node (ref "R30") (pin "1") (pinfunction "1_1") (pintype "passive"))
      (node (ref "U$1") (pin "15") (pinfunction "BAT_15") (pintype "bidirectional"))
      (node (ref "U$9") (pin "P$2") (pinfunction "P$2_P$2") (pintype "bidirectional"))
    )
    (net (code "64") (name "unconnected-(U$20-NC-Pad16)") (class "Default")
      (node (ref "U$20") (pin "16") (pinfunction "NC_16") (pintype "bidirectional"))
    )
    (net (code "65") (name "unconnected-(U$20-NC2-Pad35)") (class "Default")
      (node (ref "U$20") (pin "35") (pinfunction "NC2_35") (pintype "bidirectional"))
    )
    (net (code "66") (name "unconnected-(U$20-P0_0-Pad33)") (class "Default")
      (node (ref "U$20") (pin "33") (pinfunction "P0_0_33") (pintype "bidirectional"))
    )
    (net (code "67") (name "unconnected-(U$20-P0_1-Pad32)") (class "Default")
      (node (ref "U$20") (pin "32") (pinfunction "P0_1_32") (pintype "bidirectional"))
    )
    (net (code "68") (name "unconnected-(U$20-P0_2-Pad31)") (class "Default")
      (node (ref "U$20") (pin "31") (pinfunction "P0_2_31") (pintype "bidirectional"))
    )
    (net (code "69") (name "unconnected-(U$20-P0_3-Pad30)") (class "Default")
      (node (ref "U$20") (pin "30") (pinfunction "P0_3_30") (pintype "bidirectional"))
    )
    (net (code "70") (name "unconnected-(U$20-P0_4-Pad29)") (class "Default")
      (node (ref "U$20") (pin "29") (pinfunction "P0_4_29") (pintype "bidirectional"))
    )
    (net (code "71") (name "unconnected-(U$20-P0_5-Pad28)") (class "Default")
      (node (ref "U$20") (pin "28") (pinfunction "P0_5_28") (pintype "bidirectional"))
    )
    (net (code "72") (name "unconnected-(U$20-P1_0-Pad24)") (class "Default")
      (node (ref "U$20") (pin "24") (pinfunction "P1_0_24") (pintype "bidirectional"))
    )
    (net (code "73") (name "unconnected-(U$20-P1_2-Pad22)") (class "Default")
      (node (ref "U$20") (pin "22") (pinfunction "P1_2_22") (pintype "bidirectional"))
    )
    (net (code "74") (name "unconnected-(U$20-P1_3-Pad21)") (class "Default")
      (node (ref "U$20") (pin "21") (pinfunction "P1_3_21") (pintype "bidirectional"))
    )
    (net (code "75") (name "unconnected-(U$20-P1_4-Pad20)") (class "Default")
      (node (ref "U$20") (pin "20") (pinfunction "P1_4_20") (pintype "bidirectional"))
    )
    (net (code "76") (name "unconnected-(U$20-P1_6-Pad13)") (class "Default")
      (node (ref "U$20") (pin "13") (pinfunction "P1_6_13") (pintype "bidirectional"))
    )
    (net (code "77") (name "unconnected-(U$20-P2_0-Pad11)") (class "Default")
      (node (ref "U$20") (pin "11") (pinfunction "P2_0_11") (pintype "bidirectional"))
    )
    (net (code "78") (name "unconnected-(U$22-5A-Pad5)") (class "Default")
      (node (ref "U$22") (pin "5") (pinfunction "5A_5") (pintype "bidirectional"))
    )
    (net (code "79") (name "unconnected-(U$22-6A-Pad6)") (class "Default")
      (node (ref "U$22") (pin "6") (pinfunction "6A_6") (pintype "bidirectional"))
    )
    (net (code "80") (name "unconnected-(U$22-8A-Pad8)") (class "Default")
      (node (ref "U$22") (pin "8") (pinfunction "8A_8") (pintype "bidirectional"))
    )
    (net (code "81") (name "unconnected-(U$22-9A-Pad9)") (class "Default")
      (node (ref "U$22") (pin "9") (pinfunction "9A_9") (pintype "bidirectional"))
    )
    (net (code "82") (name "unconnected-(U$22-10A-Pad10)") (class "Default")
      (node (ref "U$22") (pin "10") (pinfunction "10A_10") (pintype "bidirectional"))
    )
    (net (code "83") (name "unconnected-(U$24-Pad6)") (class "Default")
      (node (ref "U$24") (pin "6") (pinfunction "6_6") (pintype "bidirectional"))
    )
    (net (code "84") (name "unconnected-(U$24-PadA1)") (class "Default")
      (node (ref "U$24") (pin "A1") (pinfunction "A1_A1") (pintype "bidirectional"))
    )
    (net (code "85") (name "unconnected-(U$24-PadA2)") (class "Default")
      (node (ref "U$24") (pin "A2") (pinfunction "A2_A2") (pintype "bidirectional"))
    )
    (net (code "86") (name "unconnected-(U$25-INT1-Pad6)") (class "Default")
      (node (ref "U$25") (pin "6") (pinfunction "INT1_6") (pintype "bidirectional"))
    )
    (net (code "87") (name "unconnected-(U$25-INT2-Pad5)") (class "Default")
      (node (ref "U$25") (pin "5") (pinfunction "INT2_5") (pintype "bidirectional"))
    )
    (net (code "88") (name "unconnected-(U$32-INT1-PadP$3)") (class "Default")
      (node (ref "U$32") (pin "P$3") (pinfunction "INT1_P$3") (pintype "bidirectional"))
    )
    (net (code "89") (name "unconnected-(U$32-INT2-PadP$5)") (class "Default")
      (node (ref "U$32") (pin "P$5") (pinfunction "INT2_P$5") (pintype "bidirectional"))
    )
    (net (code "90") (name "unconnected-(U$33-PadA1)") (class "Default")
      (node (ref "U$33") (pin "A1") (pinfunction "A1_A1") (pintype "bidirectional"))
    )
    (net (code "91") (name "unconnected-(U$33-PadA2)") (class "Default")
      (node (ref "U$33") (pin "A2") (pinfunction "A2_A2") (pintype "bidirectional"))
    )
  )
)
